# USB_Host_Hub.net
KiCad netlist of a schematic drawn in Altium Designer
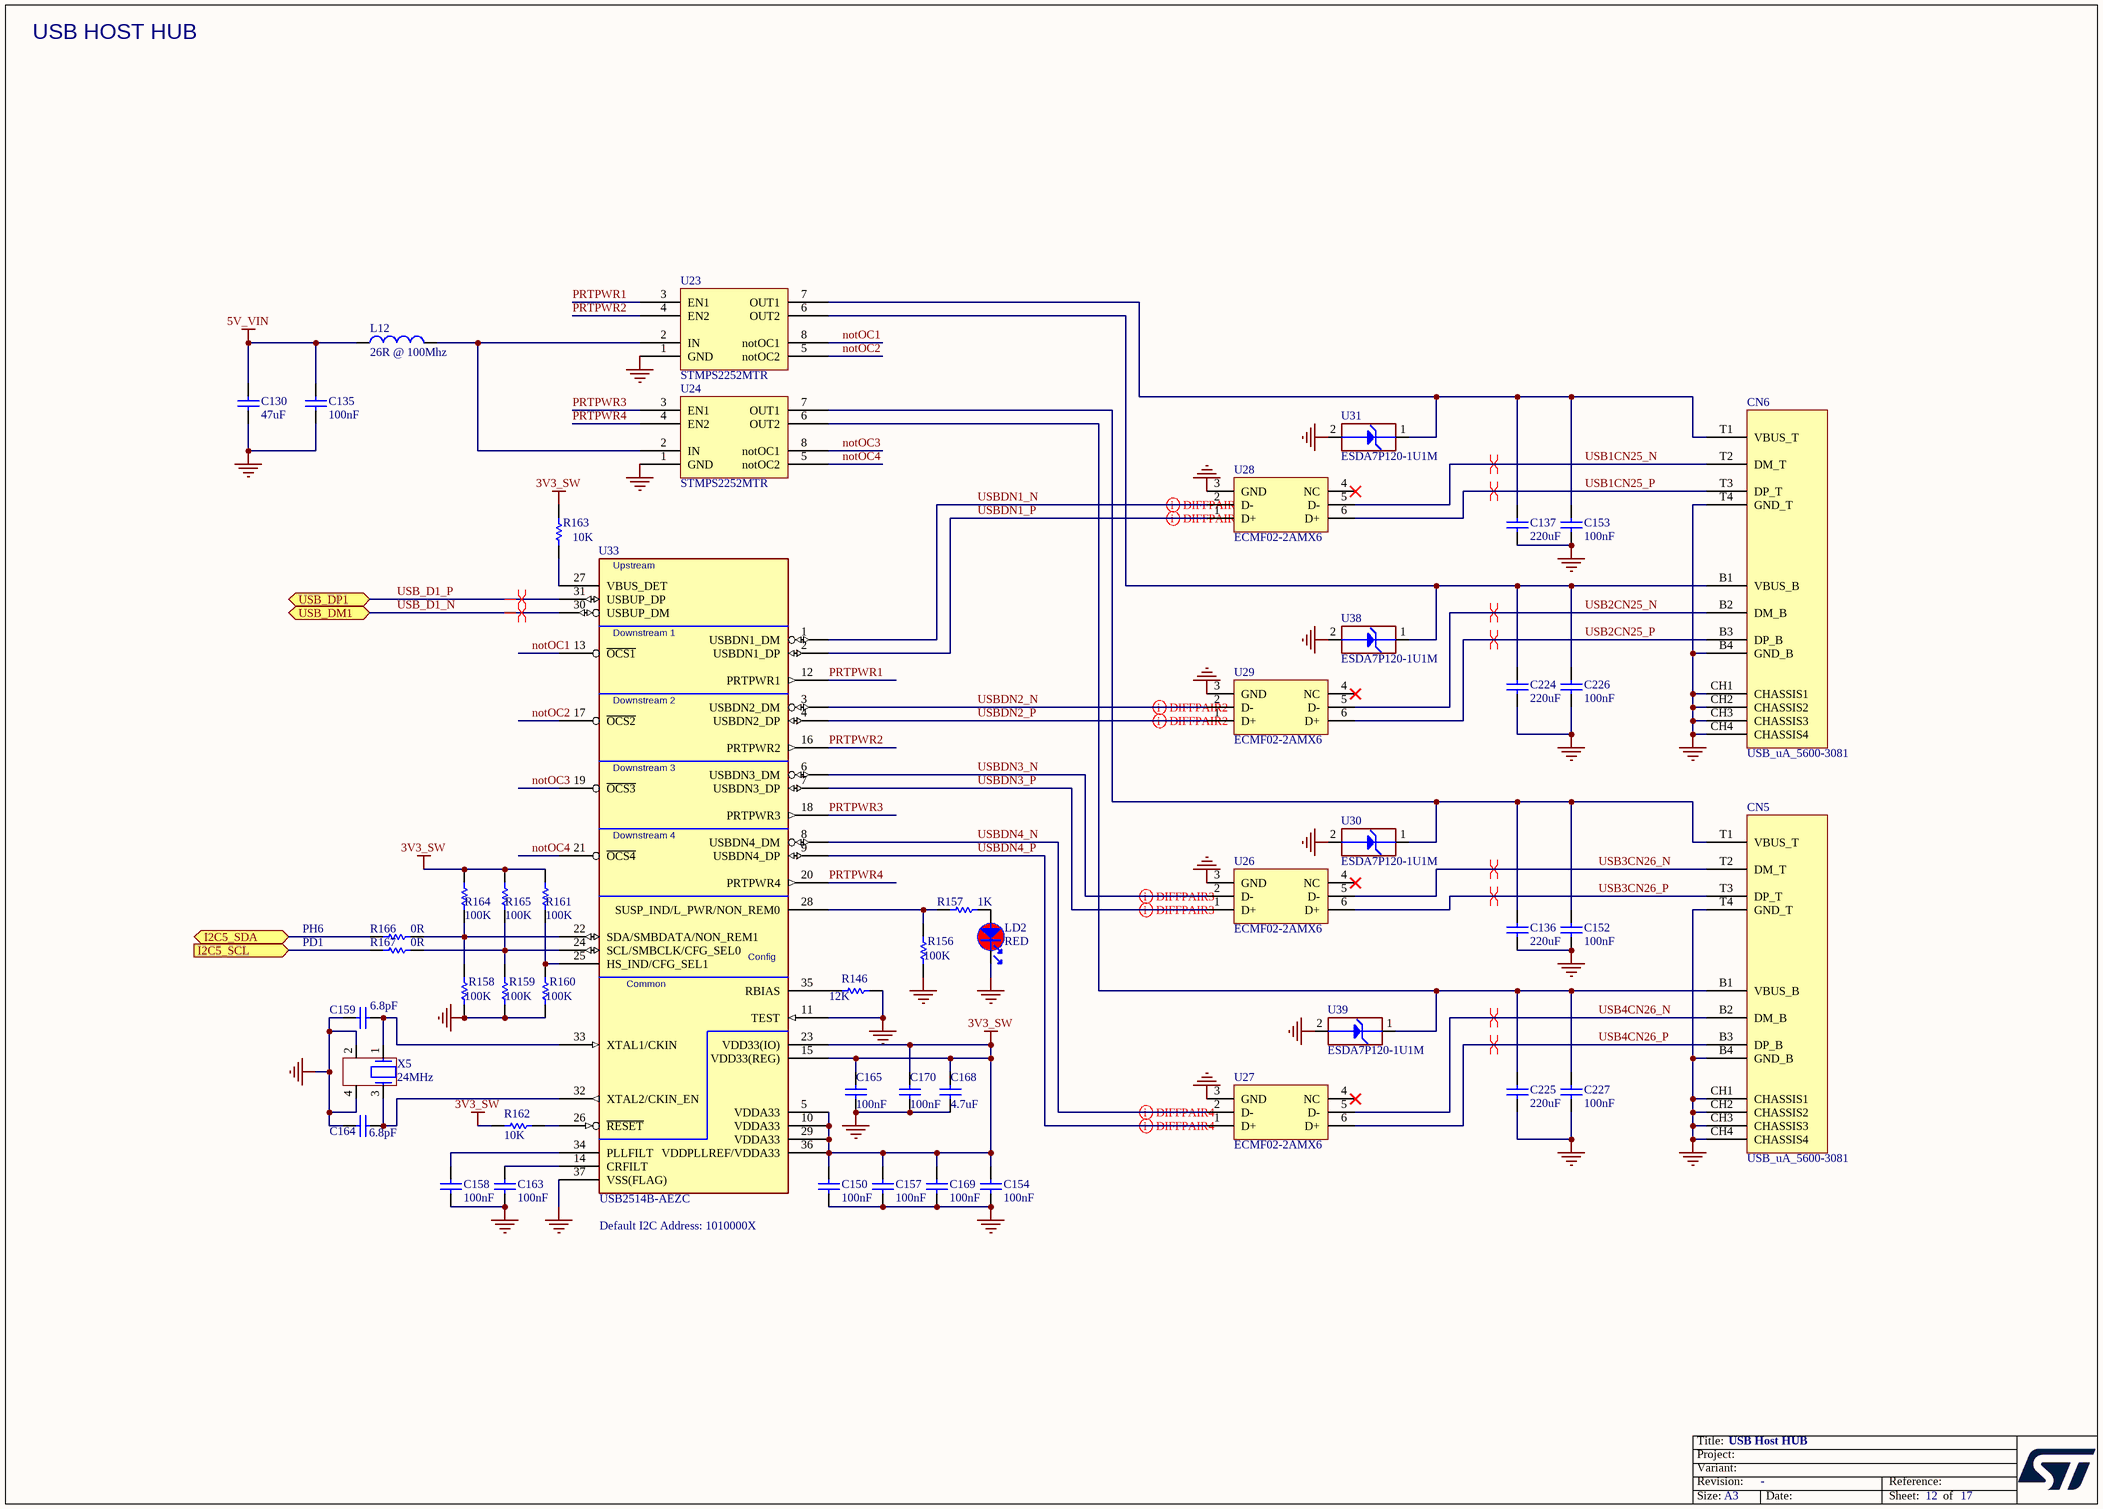
[diagram p0: USB_Host_Hub.SchDoc]

(export (version "E")
  (design (tool "Eeschema 10.0.6"))
  (components
    (comp (ref "C130")
      (value "47uF")
      (footprint "C1206_H1P6")
      (description "Capacitor, MLCC, 47uF, 25V, X5R, 20%, 1206, T=1.6mm")
      (fields (field (name "INTERNAL_PART_NUMBER") "MCD-02263") (field (name "MANUFACTURER") "MURATA"))
      (libsource (lib "MCD_PARTS_database") (part "Capacitor"))
    )
    (comp (ref "C135")
      (value "100nF")
      (footprint "C0402")
      (description "Capacitor, MLCC, 100nF, 16V, X7R, +/-10%, 0402, T=0.5mm")
      (fields
        (field (name "INTERNAL_PART_NUMBER") "MCD-00006")
        (field (name "MANUFACTURER_PART_NUMBER") "CC0402KRX7R7BB104")
      )
      (libsource (lib "MCD_PARTS_database") (part "Capacitor"))
    )
    (comp (ref "C136")
      (value "220uF")
      (footprint "C1206_H1P6")
      (description "Capacitor, MLCC, 220uF, 6V3, X5R, +/-20%, 1206, T=1.6mm")
      (fields
        (field (name "INTERNAL_PART_NUMBER") "MCD-00104")
        (field (name "MANUFACTURER_PART_NUMBER") "GRM31CR60J227ME11")
      )
      (libsource (lib "MCD_PARTS_database") (part "Capacitor"))
    )
    (comp (ref "C137")
      (value "220uF")
      (footprint "C1206_H1P6")
      (description "Capacitor, MLCC, 220uF, 6V3, X5R, +/-20%, 1206, T=1.6mm")
      (fields
        (field (name "INTERNAL_PART_NUMBER") "MCD-00104")
        (field (name "MANUFACTURER_PART_NUMBER") "GRM31CR60J227ME11")
      )
      (libsource (lib "MCD_PARTS_database") (part "Capacitor"))
    )
    (comp (ref "C150")
      (value "100nF")
      (footprint "C0402")
      (description "Capacitor, MLCC, 100nF, 16V, X7R, +/-10%, 0402, T=0.5mm")
      (fields
        (field (name "INTERNAL_PART_NUMBER") "MCD-00006")
        (field (name "MANUFACTURER_PART_NUMBER") "CC0402KRX7R7BB104")
      )
      (libsource (lib "MCD_PARTS_database") (part "Capacitor"))
    )
    (comp (ref "C152")
      (value "100nF")
      (footprint "C0402")
      (description "Capacitor, MLCC, 100nF, 16V, X7R, +/-10%, 0402, T=0.5mm")
      (fields
        (field (name "INTERNAL_PART_NUMBER") "MCD-00006")
        (field (name "MANUFACTURER_PART_NUMBER") "CC0402KRX7R7BB104")
      )
      (libsource (lib "MCD_PARTS_database") (part "Capacitor"))
    )
    (comp (ref "C153")
      (value "100nF")
      (footprint "C0402")
      (description "Capacitor, MLCC, 100nF, 16V, X7R, +/-10%, 0402, T=0.5mm")
      (fields
        (field (name "INTERNAL_PART_NUMBER") "MCD-00006")
        (field (name "MANUFACTURER_PART_NUMBER") "CC0402KRX7R7BB104")
      )
      (libsource (lib "MCD_PARTS_database") (part "Capacitor"))
    )
    (comp (ref "C154")
      (value "100nF")
      (footprint "C0402")
      (description "Capacitor, MLCC, 100nF, 16V, X7R, +/-10%, 0402, T=0.5mm")
      (fields
        (field (name "INTERNAL_PART_NUMBER") "MCD-00006")
        (field (name "MANUFACTURER_PART_NUMBER") "CC0402KRX7R7BB104")
      )
      (libsource (lib "MCD_PARTS_database") (part "Capacitor"))
    )
    (comp (ref "C157")
      (value "100nF")
      (footprint "C0402")
      (description "Capacitor, MLCC, 100nF, 16V, X7R, +/-10%, 0402, T=0.5mm")
      (fields
        (field (name "INTERNAL_PART_NUMBER") "MCD-00006")
        (field (name "MANUFACTURER_PART_NUMBER") "CC0402KRX7R7BB104")
      )
      (libsource (lib "MCD_PARTS_database") (part "Capacitor"))
    )
    (comp (ref "C158")
      (value "100nF")
      (footprint "C0402")
      (description "Capacitor, MLCC, 100nF, 16V, X7R, +/-10%, 0402, T=0.5mm")
      (fields
        (field (name "INTERNAL_PART_NUMBER") "MCD-00006")
        (field (name "MANUFACTURER_PART_NUMBER") "CC0402KRX7R7BB104")
      )
      (libsource (lib "MCD_PARTS_database") (part "Capacitor"))
    )
    (comp (ref "C159")
      (value "6.8pF")
      (footprint "C0402")
      (description "Capacitor, MLCC, 6.8pF, 50V, NPO, +/-0.25pF, 0402, T=0.5mm")
      (fields
        (field (name "INTERNAL_PART_NUMBER") "MCD-00674")
        (field (name "MANUFACTURER_PART_NUMBER") "CC0402CRNPO9BN6R8")
      )
      (libsource (lib "MCD_PARTS_database") (part "Capacitor"))
    )
    (comp (ref "C163")
      (value "100nF")
      (footprint "C0402")
      (description "Capacitor, MLCC, 100nF, 16V, X7R, +/-10%, 0402, T=0.5mm")
      (fields
        (field (name "INTERNAL_PART_NUMBER") "MCD-00006")
        (field (name "MANUFACTURER_PART_NUMBER") "CC0402KRX7R7BB104")
      )
      (libsource (lib "MCD_PARTS_database") (part "Capacitor"))
    )
    (comp (ref "C164")
      (value "6.8pF")
      (footprint "C0402")
      (description "Capacitor, MLCC, 6.8pF, 50V, NPO, +/-0.25pF, 0402, T=0.5mm")
      (fields
        (field (name "INTERNAL_PART_NUMBER") "MCD-00674")
        (field (name "MANUFACTURER_PART_NUMBER") "CC0402CRNPO9BN6R8")
      )
      (libsource (lib "MCD_PARTS_database") (part "Capacitor"))
    )
    (comp (ref "C165")
      (value "100nF")
      (footprint "C0402")
      (description "Capacitor, MLCC, 100nF, 16V, X7R, +/-10%, 0402, T=0.5mm")
      (fields
        (field (name "INTERNAL_PART_NUMBER") "MCD-00006")
        (field (name "MANUFACTURER_PART_NUMBER") "CC0402KRX7R7BB104")
      )
      (libsource (lib "MCD_PARTS_database") (part "Capacitor"))
    )
    (comp (ref "C168")
      (value "4.7uF")
      (footprint "C0402")
      (description "Capacitor, MLCC, 4.7uF, 6V3, X5R, +/-20%, 0402, T=0.5mm")
      (fields
        (field (name "INTERNAL_PART_NUMBER") "MCD-01356")
        (field (name "MANUFACTURER_PART_NUMBER") "GRM155R60J475ME47")
      )
      (libsource (lib "MCD_PARTS_database") (part "Capacitor"))
    )
    (comp (ref "C169")
      (value "100nF")
      (footprint "C0402")
      (description "Capacitor, MLCC, 100nF, 16V, X7R, +/-10%, 0402, T=0.5mm")
      (fields
        (field (name "INTERNAL_PART_NUMBER") "MCD-00006")
        (field (name "MANUFACTURER_PART_NUMBER") "CC0402KRX7R7BB104")
      )
      (libsource (lib "MCD_PARTS_database") (part "Capacitor"))
    )
    (comp (ref "C170")
      (value "100nF")
      (footprint "C0402")
      (description "Capacitor, MLCC, 100nF, 16V, X7R, +/-10%, 0402, T=0.5mm")
      (fields
        (field (name "INTERNAL_PART_NUMBER") "MCD-00006")
        (field (name "MANUFACTURER_PART_NUMBER") "CC0402KRX7R7BB104")
      )
      (libsource (lib "MCD_PARTS_database") (part "Capacitor"))
    )
    (comp (ref "C224")
      (value "220uF")
      (footprint "C1206_H1P6")
      (description "Capacitor, MLCC, 220uF, 6V3, X5R, +/-20%, 1206, T=1.6mm")
      (fields
        (field (name "INTERNAL_PART_NUMBER") "MCD-00104")
        (field (name "MANUFACTURER_PART_NUMBER") "GRM31CR60J227ME11")
      )
      (libsource (lib "MCD_PARTS_database") (part "Capacitor"))
    )
    (comp (ref "C225")
      (value "220uF")
      (footprint "C1206_H1P6")
      (description "Capacitor, MLCC, 220uF, 6V3, X5R, +/-20%, 1206, T=1.6mm")
      (fields
        (field (name "INTERNAL_PART_NUMBER") "MCD-00104")
        (field (name "MANUFACTURER_PART_NUMBER") "GRM31CR60J227ME11")
      )
      (libsource (lib "MCD_PARTS_database") (part "Capacitor"))
    )
    (comp (ref "C226")
      (value "100nF")
      (footprint "C0402")
      (description "Capacitor, MLCC, 100nF, 16V, X7R, +/-10%, 0402, T=0.5mm")
      (fields
        (field (name "INTERNAL_PART_NUMBER") "MCD-00006")
        (field (name "MANUFACTURER_PART_NUMBER") "CC0402KRX7R7BB104")
      )
      (libsource (lib "MCD_PARTS_database") (part "Capacitor"))
    )
    (comp (ref "C227")
      (value "100nF")
      (footprint "C0402")
      (description "Capacitor, MLCC, 100nF, 16V, X7R, +/-10%, 0402, T=0.5mm")
      (fields
        (field (name "INTERNAL_PART_NUMBER") "MCD-00006")
        (field (name "MANUFACTURER_PART_NUMBER") "CC0402KRX7R7BB104")
      )
      (libsource (lib "MCD_PARTS_database") (part "Capacitor"))
    )
    (comp (ref "CN5")
      (value "USB_uA_5600-3081")
      (footprint "CON_DUAL-USB-TYPE-A_CONEXCON_5600-3081")
      (description "USB_Dual-TypeA, Receptacle, 8pins, 2.5mm, RA, TH, T= 15.5mm")
      (fields
        (field (name "INTERNAL_PART_NUMBER") "MCD-00109")
        (field (name "MANUFACTURER_PART_NUMBER") "5600-3081")
      )
      (libsource (lib "MCD_PARTS_database") (part "USB_DUAL_TYPEA_5600-3081"))
    )
    (comp (ref "CN6")
      (value "USB_uA_5600-3081")
      (footprint "CON_DUAL-USB-TYPE-A_CONEXCON_5600-3081")
      (description "USB_Dual-TypeA, Receptacle, 8pins, 2.5mm, RA, TH, T= 15.5mm")
      (fields
        (field (name "INTERNAL_PART_NUMBER") "MCD-00109")
        (field (name "MANUFACTURER_PART_NUMBER") "5600-3081")
      )
      (libsource (lib "MCD_PARTS_database") (part "USB_DUAL_TYPEA_5600-3081"))
    )
    (comp (ref "L12")
      (value "26R @ 100Mhz")
      (footprint "FIL_0603_H0P65")
      (description "Ferrite bead, 26R @ 100Mhz, +/-25%, 6000mA, 0R007, 0603, T=0.75mm")
      (fields
        (field (name "INTERNAL_PART_NUMBER") "MCD-00305")
        (field (name "MANUFACTURER_PART_NUMBER") "BLM18KG260TN1")
      )
      (libsource (lib "MCD_PARTS_database") (part "BEAD"))
    )
    (comp (ref "LD2")
      (value "RED")
      (footprint "LED_0603_RED")
      (description "LED, Red, 0603")
      (fields
        (field (name "INTERNAL_PART_NUMBER") "MCD-00049")
        (field (name "MANUFACTURER_PART_NUMBER") "19-213-R6C-AP1Q2B/3T")
      )
      (libsource (lib "MCD_PARTS_database") (part "LED_red"))
    )
    (comp (ref "R146")
      (value "12K")
      (footprint "R0402")
      (description "Resistor, 12K, 0402, +/-1%, 1/16W")
      (fields
        (field (name "INTERNAL_PART_NUMBER") "MCD-00187")
        (field (name "MANUFACTURER_PART_NUMBER") "RC0402FR-0712KL")
      )
      (libsource (lib "MCD_PARTS_database") (part "Resistor"))
    )
    (comp (ref "R156")
      (value "100K")
      (footprint "R0402")
      (description "Resistor, 100K, 0402, +/-1%, 1/16W")
      (fields
        (field (name "INTERNAL_PART_NUMBER") "MCD-00059")
        (field (name "MANUFACTURER_PART_NUMBER") "RC0402FR-07100KL")
      )
      (libsource (lib "MCD_PARTS_database") (part "Resistor"))
    )
    (comp (ref "R157")
      (value "1K")
      (footprint "R0402")
      (description "Resistor, 1K, 0402, +/-1%,1/16W")
      (fields
        (field (name "INTERNAL_PART_NUMBER") "MCD-00061")
        (field (name "MANUFACTURER_PART_NUMBER") "RC0402FR-071KL")
      )
      (libsource (lib "MCD_PARTS_database") (part "Resistor"))
    )
    (comp (ref "R158")
      (value "100K")
      (footprint "R0402")
      (description "Resistor, 100K, 0402, +/-1%, 1/16W")
      (fields
        (field (name "INTERNAL_PART_NUMBER") "MCD-00059")
        (field (name "MANUFACTURER_PART_NUMBER") "RC0402FR-07100KL")
      )
      (libsource (lib "MCD_PARTS_database") (part "Resistor"))
    )
    (comp (ref "R159")
      (value "100K")
      (footprint "R0402")
      (description "Resistor, 100K, 0402, +/-1%, 1/16W")
      (fields
        (field (name "INTERNAL_PART_NUMBER") "MCD-00059")
        (field (name "MANUFACTURER_PART_NUMBER") "RC0402FR-07100KL")
      )
      (libsource (lib "MCD_PARTS_database") (part "Resistor"))
    )
    (comp (ref "R160")
      (value "100K")
      (footprint "R0402")
      (description "Resistor, 100K, 0402, +/-1%, 1/16W")
      (fields
        (field (name "INTERNAL_PART_NUMBER") "MCD-00059")
        (field (name "MANUFACTURER_PART_NUMBER") "RC0402FR-07100KL")
      )
      (libsource (lib "MCD_PARTS_database") (part "Resistor"))
    )
    (comp (ref "R161")
      (value "100K")
      (footprint "R0402")
      (description "Resistor, 100K, 0402, +/-1%, 1/16W")
      (fields
        (field (name "INTERNAL_PART_NUMBER") "MCD-00059")
        (field (name "MANUFACTURER_PART_NUMBER") "RC0402FR-07100KL")
      )
      (libsource (lib "MCD_PARTS_database") (part "Resistor"))
    )
    (comp (ref "R162")
      (value "10K")
      (footprint "R0402")
      (description "Resistor, 10K, 0402, +/-1%, 1/16W")
      (fields
        (field (name "INTERNAL_PART_NUMBER") "MCD-00053")
        (field (name "MANUFACTURER_PART_NUMBER") "RC0402FR-0710KL")
      )
      (libsource (lib "MCD_PARTS_database") (part "Resistor"))
    )
    (comp (ref "R163")
      (value "10K")
      (footprint "R0402")
      (description "Resistor, 10K, 0402, +/-1%, 1/16W")
      (fields
        (field (name "INTERNAL_PART_NUMBER") "MCD-00053")
        (field (name "MANUFACTURER_PART_NUMBER") "RC0402FR-0710KL")
      )
      (libsource (lib "MCD_PARTS_database") (part "Resistor"))
    )
    (comp (ref "R164")
      (value "100K")
      (footprint "R0402")
      (description "Resistor, 100K, 0402, +/-1%, 1/16W")
      (fields
        (field (name "INTERNAL_PART_NUMBER") "MCD-00059")
        (field (name "MANUFACTURER_PART_NUMBER") "RC0402FR-07100KL")
      )
      (libsource (lib "MCD_PARTS_database") (part "Resistor"))
    )
    (comp (ref "R165")
      (value "100K")
      (footprint "R0402")
      (description "Resistor, 100K, 0402, +/-1%, 1/16W")
      (fields
        (field (name "INTERNAL_PART_NUMBER") "MCD-00059")
        (field (name "MANUFACTURER_PART_NUMBER") "RC0402FR-07100KL")
      )
      (libsource (lib "MCD_PARTS_database") (part "Resistor"))
    )
    (comp (ref "R166")
      (value "0R")
      (footprint "R0402")
      (description "Resistor, 0R, 0402, +/-5%, 1/16W")
      (fields (field (name "INTERNAL_PART_NUMBER") "MCD-00052") (field (name "MANUFACTURER") "YAGEO"))
      (libsource (lib "MCD_PARTS_database") (part "Resistor"))
    )
    (comp (ref "R167")
      (value "0R")
      (footprint "R0402")
      (description "Resistor, 0R, 0402, +/-5%, 1/16W")
      (fields (field (name "INTERNAL_PART_NUMBER") "MCD-00052") (field (name "MANUFACTURER") "YAGEO"))
      (libsource (lib "MCD_PARTS_database") (part "Resistor"))
    )
    (comp (ref "U23")
      (value "STMPS2252MTR")
      (footprint "ICC_SO8_5X4_P127")
      (description "IC,Dual-Channel-Power-Switch,500mA,100mR,SO8")
      (fields
        (field (name "INTERNAL_PART_NUMBER") "MCD-00123")
        (field (name "MANUFACTURER") "STMICROELECTRONICS")
      )
      (libsource (lib "MCD_PARTS_database") (part "STMPS2252MTR"))
    )
    (comp (ref "U24")
      (value "STMPS2252MTR")
      (footprint "ICC_SO8_5X4_P127")
      (description "IC,Dual-Channel-Power-Switch,500mA,100mR,SO8")
      (fields
        (field (name "INTERNAL_PART_NUMBER") "MCD-00123")
        (field (name "MANUFACTURER") "STMICROELECTRONICS")
      )
      (libsource (lib "MCD_PARTS_database") (part "STMPS2252MTR"))
    )
    (comp (ref "U26")
      (value "ECMF02-2AMX6")
      (footprint "ESD_QFN-6L_1P7X1P5_P050")
      (description "Common mode filter with ESD protection for USB 2.0 interface")
      (fields
        (field (name "INTERNAL_PART_NUMBER") "MCD-00649")
        (field (name "MANUFACTURER") "STMICROELECTRONICS")
      )
      (libsource (lib "MCD_PARTS_database") (part "ECMF02-2AMX6"))
    )
    (comp (ref "U27")
      (value "ECMF02-2AMX6")
      (footprint "ESD_QFN-6L_1P7X1P5_P050")
      (description "Common mode filter with ESD protection for USB 2.0 interface")
      (fields
        (field (name "INTERNAL_PART_NUMBER") "MCD-00649")
        (field (name "MANUFACTURER") "STMICROELECTRONICS")
      )
      (libsource (lib "MCD_PARTS_database") (part "ECMF02-2AMX6"))
    )
    (comp (ref "U28")
      (value "ECMF02-2AMX6")
      (footprint "ESD_QFN-6L_1P7X1P5_P050")
      (description "Common mode filter with ESD protection for USB 2.0 interface")
      (fields
        (field (name "INTERNAL_PART_NUMBER") "MCD-00649")
        (field (name "MANUFACTURER") "STMICROELECTRONICS")
      )
      (libsource (lib "MCD_PARTS_database") (part "ECMF02-2AMX6"))
    )
    (comp (ref "U29")
      (value "ECMF02-2AMX6")
      (footprint "ESD_QFN-6L_1P7X1P5_P050")
      (description "Common mode filter with ESD protection for USB 2.0 interface")
      (fields
        (field (name "INTERNAL_PART_NUMBER") "MCD-00649")
        (field (name "MANUFACTURER") "STMICROELECTRONICS")
      )
      (libsource (lib "MCD_PARTS_database") (part "ECMF02-2AMX6"))
    )
    (comp (ref "U30")
      (value "ESDA7P120-1U1M")
      (footprint "ESD_QFN1610_2N_1K_2A")
      (description "High power transient voltage suppressor")
      (fields
        (field (name "INTERNAL_PART_NUMBER") "MCD-01026")
        (field (name "MANUFACTURER") "STMICROELECTRONICS")
      )
      (libsource (lib "MCD_PARTS_database") (part "ESD-TRANSIL"))
    )
    (comp (ref "U31")
      (value "ESDA7P120-1U1M")
      (footprint "ESD_QFN1610_2N_1K_2A")
      (description "High power transient voltage suppressor")
      (fields
        (field (name "INTERNAL_PART_NUMBER") "MCD-01026")
        (field (name "MANUFACTURER") "STMICROELECTRONICS")
      )
      (libsource (lib "MCD_PARTS_database") (part "ESD-TRANSIL"))
    )
    (comp (ref "U33")
      (value "USB2514B-AEZC")
      (footprint "ICC_QFN36-EPAD_6X6_P050")
      (description "USB HUB 2,0 Controller")
      (fields (field (name "INTERNAL_PART_NUMBER") "MCD-00145") (field (name "MANUFACTURER") "MICROCHIP"))
      (libsource (lib "MCD_PARTS_database") (part "USB2514B-AEZC"))
    )
    (comp (ref "U38")
      (value "ESDA7P120-1U1M")
      (footprint "ESD_QFN1610_2N_1K_2A")
      (description "High power transient voltage suppressor")
      (fields
        (field (name "INTERNAL_PART_NUMBER") "MCD-01026")
        (field (name "MANUFACTURER") "STMICROELECTRONICS")
      )
      (libsource (lib "MCD_PARTS_database") (part "ESD-TRANSIL"))
    )
    (comp (ref "U39")
      (value "ESDA7P120-1U1M")
      (footprint "ESD_QFN1610_2N_1K_2A")
      (description "High power transient voltage suppressor")
      (fields
        (field (name "INTERNAL_PART_NUMBER") "MCD-01026")
        (field (name "MANUFACTURER") "STMICROELECTRONICS")
      )
      (libsource (lib "MCD_PARTS_database") (part "ESD-TRANSIL"))
    )
    (comp (ref "X5")
      (value "24MHz")
      (footprint "CRY_NX2016SA_4P")
      (description "Crystal, 24MHz, 6pF, +/-20ppm, 80R, 2x1.6mm")
      (fields
        (field (name "INTERNAL_PART_NUMBER") "MCD-01036")
        (field (name "MANUFACTURER_PART_NUMBER") "NX2016SA-24MHZ-EXS00A-CS10820")
      )
      (libsource (lib "MCD_PARTS_database") (part "XTAL_4_PINS"))
    )
  )
  (nets
    (net (code "1") (name "/I2C5_SCL") (class "Default")
      (node (ref "R167") (pin "1") (pinfunction "1_1") (pintype "passive"))
    )
    (net (code "2") (name "/I2C5_SDA") (class "Default")
      (node (ref "R166") (pin "1") (pinfunction "1_1") (pintype "passive"))
    )
    (net (code "3") (name "/PRTPWR1") (class "Default")
      (node (ref "U23") (pin "3") (pinfunction "EN1_3") (pintype "passive"))
      (node (ref "U33") (pin "12") (pinfunction "PRTPWR1_12") (pintype "output"))
    )
    (net (code "4") (name "/PRTPWR2") (class "Default")
      (node (ref "U23") (pin "4") (pinfunction "EN2_4") (pintype "passive"))
      (node (ref "U33") (pin "16") (pinfunction "PRTPWR2_16") (pintype "output"))
    )
    (net (code "5") (name "/PRTPWR3") (class "Default")
      (node (ref "U24") (pin "3") (pinfunction "EN1_3") (pintype "passive"))
      (node (ref "U33") (pin "18") (pinfunction "PRTPWR3_18") (pintype "output"))
    )
    (net (code "6") (name "/PRTPWR4") (class "Default")
      (node (ref "U24") (pin "4") (pinfunction "EN2_4") (pintype "passive"))
      (node (ref "U33") (pin "20") (pinfunction "PRTPWR4_20") (pintype "output"))
    )
    (net (code "7") (name "/USB1CN25_N") (class "Default")
      (node (ref "CN6") (pin "T2") (pinfunction "DM_T_T2") (pintype "passive"))
      (node (ref "U28") (pin "5") (pinfunction "D-_5") (pintype "passive"))
    )
    (net (code "8") (name "/USB1CN25_P") (class "Default")
      (node (ref "CN6") (pin "T3") (pinfunction "DP_T_T3") (pintype "passive"))
      (node (ref "U28") (pin "6") (pinfunction "D+_6") (pintype "passive"))
    )
    (net (code "9") (name "/USB2CN25_N") (class "Default")
      (node (ref "CN6") (pin "B2") (pinfunction "DM_B_B2") (pintype "passive"))
      (node (ref "U29") (pin "5") (pinfunction "D-_5") (pintype "passive"))
    )
    (net (code "10") (name "/USB2CN25_P") (class "Default")
      (node (ref "CN6") (pin "B3") (pinfunction "DP_B_B3") (pintype "passive"))
      (node (ref "U29") (pin "6") (pinfunction "D+_6") (pintype "passive"))
    )
    (net (code "11") (name "/USB3CN26_N") (class "Default")
      (node (ref "CN5") (pin "T2") (pinfunction "DM_T_T2") (pintype "passive"))
      (node (ref "U26") (pin "5") (pinfunction "D-_5") (pintype "passive"))
    )
    (net (code "12") (name "/USB3CN26_P") (class "Default")
      (node (ref "CN5") (pin "T3") (pinfunction "DP_T_T3") (pintype "passive"))
      (node (ref "U26") (pin "6") (pinfunction "D+_6") (pintype "passive"))
    )
    (net (code "13") (name "/USB4CN26_N") (class "Default")
      (node (ref "CN5") (pin "B2") (pinfunction "DM_B_B2") (pintype "passive"))
      (node (ref "U27") (pin "5") (pinfunction "D-_5") (pintype "passive"))
    )
    (net (code "14") (name "/USB4CN26_P") (class "Default")
      (node (ref "CN5") (pin "B3") (pinfunction "DP_B_B3") (pintype "passive"))
      (node (ref "U27") (pin "6") (pinfunction "D+_6") (pintype "passive"))
    )
    (net (code "15") (name "/USBDN1_N") (class "Default")
      (node (ref "U28") (pin "2") (pinfunction "D-_2") (pintype "passive"))
      (node (ref "U33") (pin "1") (pinfunction "USBDN1_DM_1") (pintype "bidirectional"))
    )
    (net (code "16") (name "/USBDN1_P") (class "Default")
      (node (ref "U28") (pin "1") (pinfunction "D+_1") (pintype "passive"))
      (node (ref "U33") (pin "2") (pinfunction "USBDN1_DP_2") (pintype "bidirectional"))
    )
    (net (code "17") (name "/USBDN2_N") (class "Default")
      (node (ref "U29") (pin "2") (pinfunction "D-_2") (pintype "passive"))
      (node (ref "U33") (pin "3") (pinfunction "USBDN2_DM_3") (pintype "bidirectional"))
    )
    (net (code "18") (name "/USBDN2_P") (class "Default")
      (node (ref "U29") (pin "1") (pinfunction "D+_1") (pintype "passive"))
      (node (ref "U33") (pin "4") (pinfunction "USBDN2_DP_4") (pintype "bidirectional"))
    )
    (net (code "19") (name "/USBDN3_N") (class "Default")
      (node (ref "U26") (pin "2") (pinfunction "D-_2") (pintype "passive"))
      (node (ref "U33") (pin "6") (pinfunction "USBDN3_DM_6") (pintype "bidirectional"))
    )
    (net (code "20") (name "/USBDN3_P") (class "Default")
      (node (ref "U26") (pin "1") (pinfunction "D+_1") (pintype "passive"))
      (node (ref "U33") (pin "7") (pinfunction "USBDN3_DP_7") (pintype "bidirectional"))
    )
    (net (code "21") (name "/USBDN4_N") (class "Default")
      (node (ref "U27") (pin "2") (pinfunction "D-_2") (pintype "passive"))
      (node (ref "U33") (pin "8") (pinfunction "USBDN4_DM_8") (pintype "bidirectional"))
    )
    (net (code "22") (name "/USBDN4_P") (class "Default")
      (node (ref "U27") (pin "1") (pinfunction "D+_1") (pintype "passive"))
      (node (ref "U33") (pin "9") (pinfunction "USBDN4_DP_9") (pintype "bidirectional"))
    )
    (net (code "23") (name "/USB_D1_N") (class "Default")
      (node (ref "U33") (pin "30") (pinfunction "USBUP_DM_30") (pintype "bidirectional"))
    )
    (net (code "24") (name "/USB_D1_P") (class "Default")
      (node (ref "U33") (pin "31") (pinfunction "USBUP_DP_31") (pintype "bidirectional"))
    )
    (net (code "25") (name "/notOC1") (class "Default")
      (node (ref "U23") (pin "8") (pinfunction "notOC1_8") (pintype "passive"))
      (node (ref "U33") (pin "13") (pinfunction "~{OCS1}_13") (pintype "passive"))
    )
    (net (code "26") (name "/notOC2") (class "Default")
      (node (ref "U23") (pin "5") (pinfunction "notOC2_5") (pintype "passive"))
      (node (ref "U33") (pin "17") (pinfunction "~{OCS2}_17") (pintype "passive"))
    )
    (net (code "27") (name "/notOC3") (class "Default")
      (node (ref "U24") (pin "8") (pinfunction "notOC1_8") (pintype "passive"))
      (node (ref "U33") (pin "19") (pinfunction "~{OCS3}_19") (pintype "passive"))
    )
    (net (code "28") (name "/notOC4") (class "Default")
      (node (ref "U24") (pin "5") (pinfunction "notOC2_5") (pintype "passive"))
      (node (ref "U33") (pin "21") (pinfunction "~{OCS4}_21") (pintype "passive"))
    )
    (net (code "29") (name "3V3_SW") (class "Default")
      (node (ref "C150") (pin "2") (pinfunction "2_2") (pintype "passive"))
      (node (ref "C154") (pin "2") (pinfunction "2_2") (pintype "passive"))
      (node (ref "C157") (pin "2") (pinfunction "2_2") (pintype "passive"))
      (node (ref "C165") (pin "2") (pinfunction "2_2") (pintype "passive"))
      (node (ref "C168") (pin "2") (pinfunction "2_2") (pintype "passive"))
      (node (ref "C169") (pin "2") (pinfunction "2_2") (pintype "passive"))
      (node (ref "C170") (pin "2") (pinfunction "2_2") (pintype "passive"))
      (node (ref "R161") (pin "2") (pinfunction "2_2") (pintype "passive"))
      (node (ref "R162") (pin "1") (pinfunction "1_1") (pintype "passive"))
      (node (ref "R163") (pin "2") (pinfunction "2_2") (pintype "passive"))
      (node (ref "R164") (pin "2") (pinfunction "2_2") (pintype "passive"))
      (node (ref "R165") (pin "2") (pinfunction "2_2") (pintype "passive"))
      (node (ref "U33") (pin "10") (pinfunction "VDDA33_10") (pintype "power_in"))
      (node (ref "U33") (pin "15") (pinfunction "VDD33(REG)_15") (pintype "power_in"))
      (node (ref "U33") (pin "23") (pinfunction "VDD33(IO)_23") (pintype "power_in"))
      (node (ref "U33") (pin "29") (pinfunction "VDDA33_29") (pintype "power_in"))
      (node (ref "U33") (pin "36") (pinfunction "VDDPLLREF/VDDA33_36") (pintype "power_in"))
      (node (ref "U33") (pin "5") (pinfunction "VDDA33_5") (pintype "power_in"))
    )
    (net (code "30") (name "5V_VIN") (class "Default")
      (node (ref "C130") (pin "2") (pinfunction "2_2") (pintype "passive"))
      (node (ref "C135") (pin "2") (pinfunction "2_2") (pintype "passive"))
      (node (ref "L12") (pin "1") (pinfunction "1_1") (pintype "passive"))
    )
    (net (code "31") (name "GND") (class "Default")
      (node (ref "C130") (pin "1") (pinfunction "1_1") (pintype "passive"))
      (node (ref "C135") (pin "1") (pinfunction "1_1") (pintype "passive"))
      (node (ref "C136") (pin "1") (pinfunction "1_1") (pintype "passive"))
      (node (ref "C137") (pin "1") (pinfunction "1_1") (pintype "passive"))
      (node (ref "C150") (pin "1") (pinfunction "1_1") (pintype "passive"))
      (node (ref "C152") (pin "1") (pinfunction "1_1") (pintype "passive"))
      (node (ref "C153") (pin "1") (pinfunction "1_1") (pintype "passive"))
      (node (ref "C154") (pin "1") (pinfunction "1_1") (pintype "passive"))
      (node (ref "C157") (pin "1") (pinfunction "1_1") (pintype "passive"))
      (node (ref "C158") (pin "1") (pinfunction "1_1") (pintype "passive"))
      (node (ref "C159") (pin "1") (pinfunction "1_1") (pintype "passive"))
      (node (ref "C163") (pin "1") (pinfunction "1_1") (pintype "passive"))
      (node (ref "C164") (pin "1") (pinfunction "1_1") (pintype "passive"))
      (node (ref "C165") (pin "1") (pinfunction "1_1") (pintype "passive"))
      (node (ref "C168") (pin "1") (pinfunction "1_1") (pintype "passive"))
      (node (ref "C169") (pin "1") (pinfunction "1_1") (pintype "passive"))
      (node (ref "C170") (pin "1") (pinfunction "1_1") (pintype "passive"))
      (node (ref "C224") (pin "1") (pinfunction "1_1") (pintype "passive"))
      (node (ref "C225") (pin "1") (pinfunction "1_1") (pintype "passive"))
      (node (ref "C226") (pin "1") (pinfunction "1_1") (pintype "passive"))
      (node (ref "C227") (pin "1") (pinfunction "1_1") (pintype "passive"))
      (node (ref "CN5") (pin "B4") (pinfunction "GND_B_B4") (pintype "passive"))
      (node (ref "CN5") (pin "CH1") (pinfunction "CHASSIS1_CH1") (pintype "passive"))
      (node (ref "CN5") (pin "CH2") (pinfunction "CHASSIS2_CH2") (pintype "passive"))
      (node (ref "CN5") (pin "CH3") (pinfunction "CHASSIS3_CH3") (pintype "passive"))
      (node (ref "CN5") (pin "CH4") (pinfunction "CHASSIS4_CH4") (pintype "passive"))
      (node (ref "CN5") (pin "T4") (pinfunction "GND_T_T4") (pintype "passive"))
      (node (ref "CN6") (pin "B4") (pinfunction "GND_B_B4") (pintype "passive"))
      (node (ref "CN6") (pin "CH1") (pinfunction "CHASSIS1_CH1") (pintype "passive"))
      (node (ref "CN6") (pin "CH2") (pinfunction "CHASSIS2_CH2") (pintype "passive"))
      (node (ref "CN6") (pin "CH3") (pinfunction "CHASSIS3_CH3") (pintype "passive"))
      (node (ref "CN6") (pin "CH4") (pinfunction "CHASSIS4_CH4") (pintype "passive"))
      (node (ref "CN6") (pin "T4") (pinfunction "GND_T_T4") (pintype "passive"))
      (node (ref "LD2") (pin "2") (pintype "passive"))
      (node (ref "R146") (pin "1") (pinfunction "1_1") (pintype "passive"))
      (node (ref "R156") (pin "1") (pinfunction "1_1") (pintype "passive"))
      (node (ref "R158") (pin "1") (pinfunction "1_1") (pintype "passive"))
      (node (ref "R159") (pin "1") (pinfunction "1_1") (pintype "passive"))
      (node (ref "R160") (pin "1") (pinfunction "1_1") (pintype "passive"))
      (node (ref "U23") (pin "1") (pinfunction "GND_1") (pintype "passive"))
      (node (ref "U24") (pin "1") (pinfunction "GND_1") (pintype "passive"))
      (node (ref "U26") (pin "3") (pinfunction "GND_3") (pintype "passive"))
      (node (ref "U27") (pin "3") (pinfunction "GND_3") (pintype "passive"))
      (node (ref "U28") (pin "3") (pinfunction "GND_3") (pintype "passive"))
      (node (ref "U29") (pin "3") (pinfunction "GND_3") (pintype "passive"))
      (node (ref "U30") (pin "2") (pinfunction "GND_2") (pintype "passive"))
      (node (ref "U31") (pin "2") (pinfunction "GND_2") (pintype "passive"))
      (node (ref "U33") (pin "11") (pinfunction "TEST_11") (pintype "input"))
      (node (ref "U33") (pin "37") (pinfunction "VSS(FLAG)_37") (pintype "power_in"))
      (node (ref "U38") (pin "2") (pinfunction "GND_2") (pintype "passive"))
      (node (ref "U39") (pin "2") (pinfunction "GND_2") (pintype "passive"))
      (node (ref "X5") (pin "2") (pinfunction "2_2") (pintype "passive"))
      (node (ref "X5") (pin "4") (pinfunction "4_4") (pintype "passive"))
    )
    (net (code "32") (name "Net-(CN5-VBUS_B)") (class "Default")
      (node (ref "C225") (pin "2") (pinfunction "2_2") (pintype "passive"))
      (node (ref "C227") (pin "2") (pinfunction "2_2") (pintype "passive"))
      (node (ref "CN5") (pin "B1") (pinfunction "VBUS_B_B1") (pintype "passive"))
      (node (ref "U24") (pin "6") (pinfunction "OUT2_6") (pintype "passive"))
      (node (ref "U39") (pin "1") (pinfunction "IO1_1") (pintype "passive"))
    )
    (net (code "33") (name "Net-(CN5-VBUS_T)") (class "Default")
      (node (ref "C136") (pin "2") (pinfunction "2_2") (pintype "passive"))
      (node (ref "C152") (pin "2") (pinfunction "2_2") (pintype "passive"))
      (node (ref "CN5") (pin "T1") (pinfunction "VBUS_T_T1") (pintype "passive"))
      (node (ref "U24") (pin "7") (pinfunction "OUT1_7") (pintype "passive"))
      (node (ref "U30") (pin "1") (pinfunction "IO1_1") (pintype "passive"))
    )
    (net (code "34") (name "Net-(CN6-VBUS_B)") (class "Default")
      (node (ref "C224") (pin "2") (pinfunction "2_2") (pintype "passive"))
      (node (ref "C226") (pin "2") (pinfunction "2_2") (pintype "passive"))
      (node (ref "CN6") (pin "B1") (pinfunction "VBUS_B_B1") (pintype "passive"))
      (node (ref "U23") (pin "6") (pinfunction "OUT2_6") (pintype "passive"))
      (node (ref "U38") (pin "1") (pinfunction "IO1_1") (pintype "passive"))
    )
    (net (code "35") (name "Net-(CN6-VBUS_T)") (class "Default")
      (node (ref "C137") (pin "2") (pinfunction "2_2") (pintype "passive"))
      (node (ref "C153") (pin "2") (pinfunction "2_2") (pintype "passive"))
      (node (ref "CN6") (pin "T1") (pinfunction "VBUS_T_T1") (pintype "passive"))
      (node (ref "U23") (pin "7") (pinfunction "OUT1_7") (pintype "passive"))
      (node (ref "U31") (pin "1") (pinfunction "IO1_1") (pintype "passive"))
    )
    (net (code "36") (name "Net-(LD2-Pad1)") (class "Default")
      (node (ref "LD2") (pin "1") (pintype "passive"))
      (node (ref "R157") (pin "1") (pinfunction "1_1") (pintype "passive"))
    )
    (net (code "37") (name "Net-(U23-IN)") (class "Default")
      (node (ref "L12") (pin "2") (pinfunction "2_2") (pintype "passive"))
      (node (ref "U23") (pin "2") (pinfunction "IN_2") (pintype "passive"))
      (node (ref "U24") (pin "2") (pinfunction "IN_2") (pintype "passive"))
    )
    (net (code "38") (name "Net-(U33-CRFILT)") (class "Default")
      (node (ref "C163") (pin "2") (pinfunction "2_2") (pintype "passive"))
      (node (ref "U33") (pin "14") (pinfunction "CRFILT_14") (pintype "power_in"))
    )
    (net (code "39") (name "Net-(U33-HS_IND{slash}CFG_SEL1)") (class "Default")
      (node (ref "R160") (pin "2") (pinfunction "2_2") (pintype "passive"))
      (node (ref "R161") (pin "1") (pinfunction "1_1") (pintype "passive"))
      (node (ref "U33") (pin "25") (pinfunction "HS_IND/CFG_SEL1_25") (pintype "passive"))
    )
    (net (code "40") (name "Net-(U33-PLLFILT)") (class "Default")
      (node (ref "C158") (pin "2") (pinfunction "2_2") (pintype "passive"))
      (node (ref "U33") (pin "34") (pinfunction "PLLFILT_34") (pintype "power_in"))
    )
    (net (code "41") (name "Net-(U33-RBIAS)") (class "Default")
      (node (ref "R146") (pin "2") (pinfunction "2_2") (pintype "passive"))
      (node (ref "U33") (pin "35") (pinfunction "RBIAS_35") (pintype "passive"))
    )
    (net (code "42") (name "Net-(U33-SCL{slash}SMBCLK{slash}CFG_SEL0)") (class "Default")
      (node (ref "R159") (pin "2") (pinfunction "2_2") (pintype "passive"))
      (node (ref "R165") (pin "1") (pinfunction "1_1") (pintype "passive"))
      (node (ref "R167") (pin "2") (pinfunction "2_2") (pintype "passive"))
      (node (ref "U33") (pin "24") (pinfunction "SCL/SMBCLK/CFG_SEL0_24") (pintype "bidirectional"))
    )
    (net (code "43") (name "Net-(U33-SDA{slash}SMBDATA{slash}NON_REM1)") (class "Default")
      (node (ref "R158") (pin "2") (pinfunction "2_2") (pintype "passive"))
      (node (ref "R164") (pin "1") (pinfunction "1_1") (pintype "passive"))
      (node (ref "R166") (pin "2") (pinfunction "2_2") (pintype "passive"))
      (node (ref "U33") (pin "22") (pinfunction "SDA/SMBDATA/NON_REM1_22") (pintype "bidirectional"))
    )
    (net (code "44") (name "Net-(U33-SUSP_IND{slash}L_PWR{slash}NON_REM0)") (class "Default")
      (node (ref "R156") (pin "2") (pinfunction "2_2") (pintype "passive"))
      (node (ref "R157") (pin "2") (pinfunction "2_2") (pintype "passive"))
      (node (ref "U33") (pin "28") (pinfunction "SUSP_IND/L_PWR/NON_REM0_28") (pintype "passive"))
    )
    (net (code "45") (name "Net-(U33-VBUS_DET)") (class "Default")
      (node (ref "R163") (pin "1") (pinfunction "1_1") (pintype "passive"))
      (node (ref "U33") (pin "27") (pinfunction "VBUS_DET_27") (pintype "passive"))
    )
    (net (code "46") (name "Net-(U33-XTAL1{slash}CKIN)") (class "Default")
      (node (ref "C159") (pin "2") (pinfunction "2_2") (pintype "passive"))
      (node (ref "U33") (pin "33") (pinfunction "XTAL1/CKIN_33") (pintype "input"))
      (node (ref "X5") (pin "1") (pinfunction "1_1") (pintype "passive"))
    )
    (net (code "47") (name "Net-(U33-XTAL2{slash}CKIN_EN)") (class "Default")
      (node (ref "C164") (pin "2") (pinfunction "2_2") (pintype "passive"))
      (node (ref "U33") (pin "32") (pinfunction "XTAL2/CKIN_EN_32") (pintype "output"))
      (node (ref "X5") (pin "3") (pinfunction "3_3") (pintype "passive"))
    )
    (net (code "48") (name "Net-(U33-~{RESET})") (class "Default")
      (node (ref "R162") (pin "2") (pinfunction "2_2") (pintype "passive"))
      (node (ref "U33") (pin "26") (pinfunction "~{RESET}_26") (pintype "input"))
    )
    (net (code "49") (name "unconnected-(U26-NC-Pad4)") (class "Default")
      (node (ref "U26") (pin "4") (pinfunction "NC_4") (pintype "passive+no_connect"))
    )
    (net (code "50") (name "unconnected-(U27-NC-Pad4)") (class "Default")
      (node (ref "U27") (pin "4") (pinfunction "NC_4") (pintype "passive+no_connect"))
    )
    (net (code "51") (name "unconnected-(U28-NC-Pad4)") (class "Default")
      (node (ref "U28") (pin "4") (pinfunction "NC_4") (pintype "passive+no_connect"))
    )
    (net (code "52") (name "unconnected-(U29-NC-Pad4)") (class "Default")
      (node (ref "U29") (pin "4") (pinfunction "NC_4") (pintype "passive+no_connect"))
    )
  )
)
